# UDB5.net
KiCad netlist of a schematic drawn in EAGLE
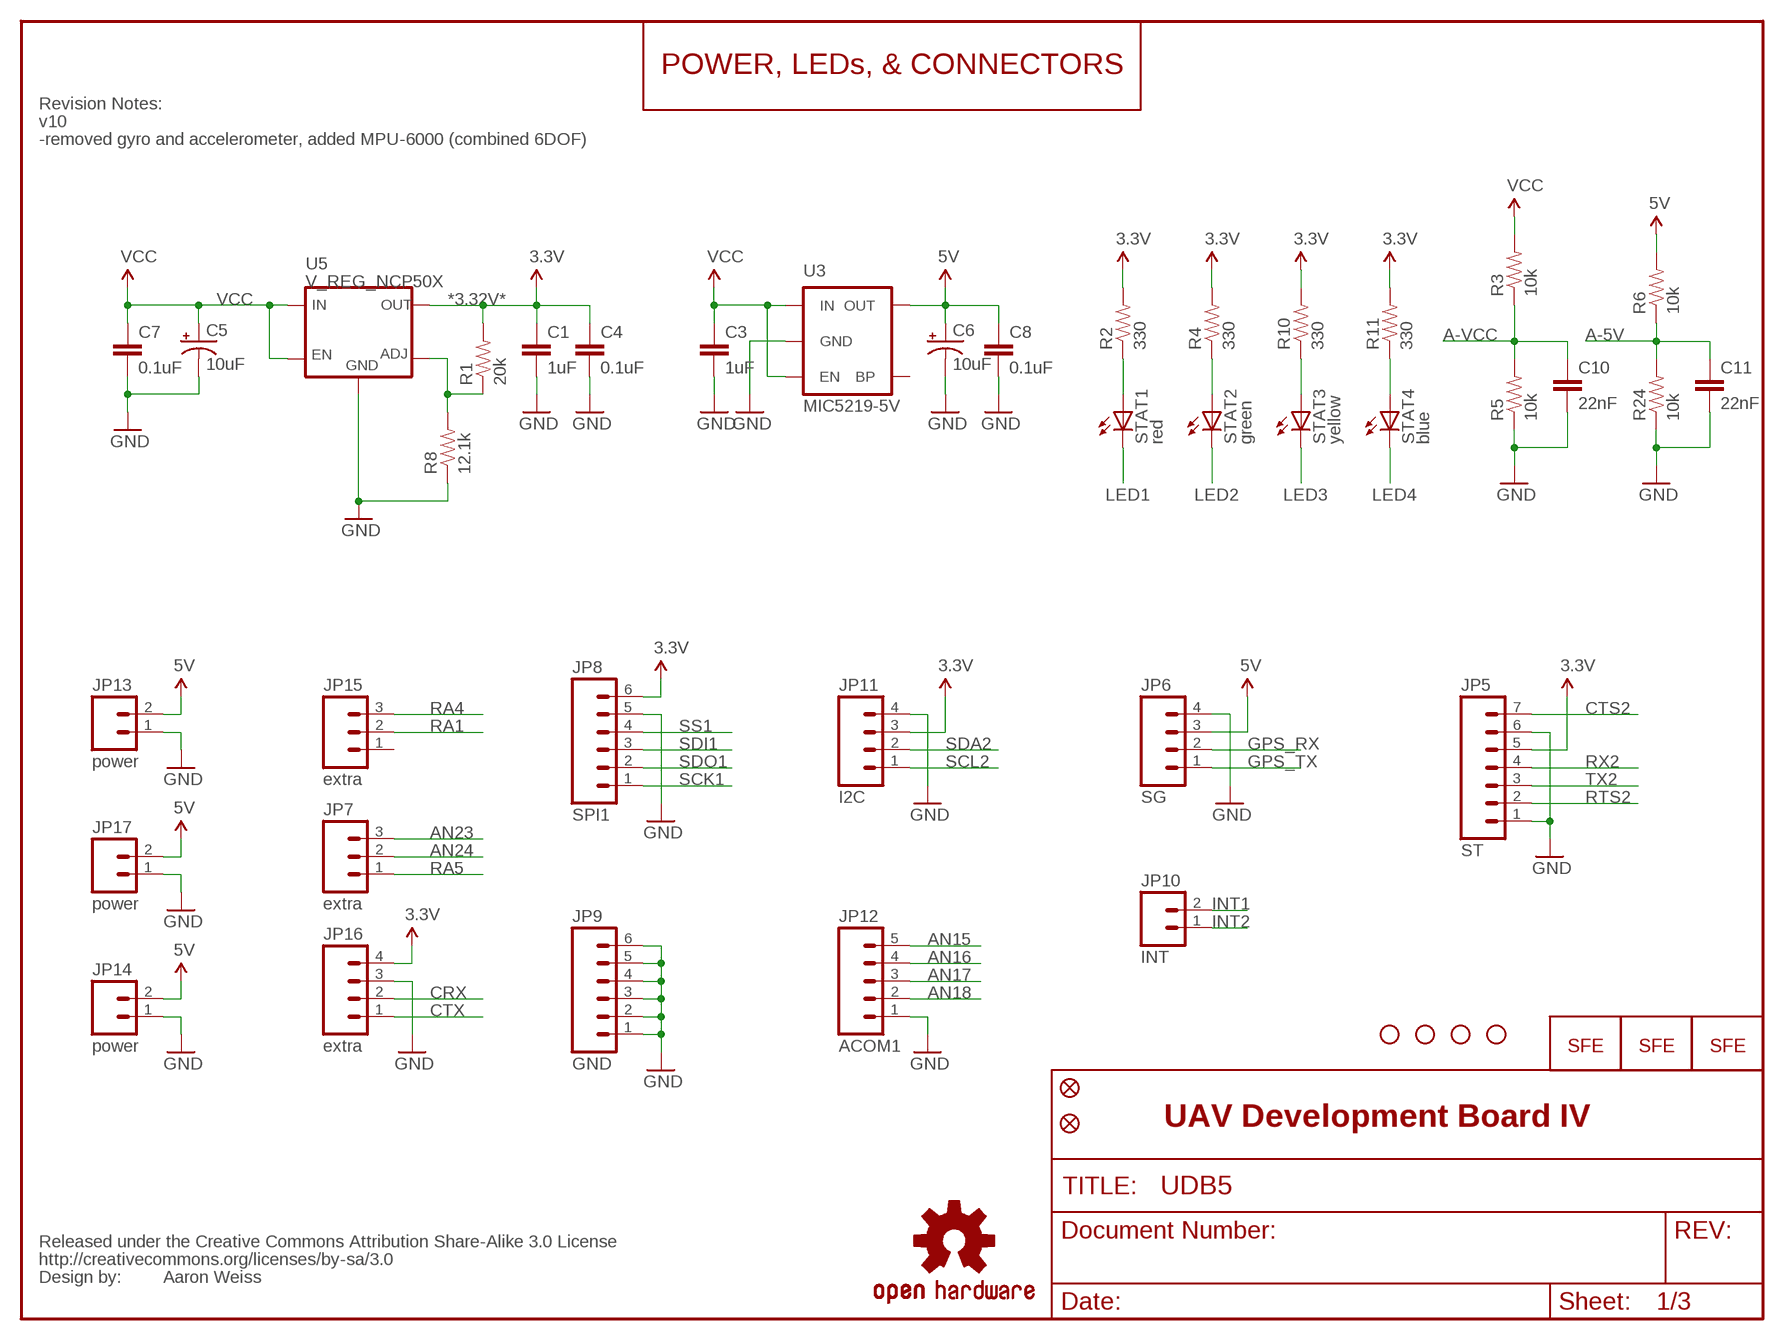
[diagram p0: schematic, sheet 1]
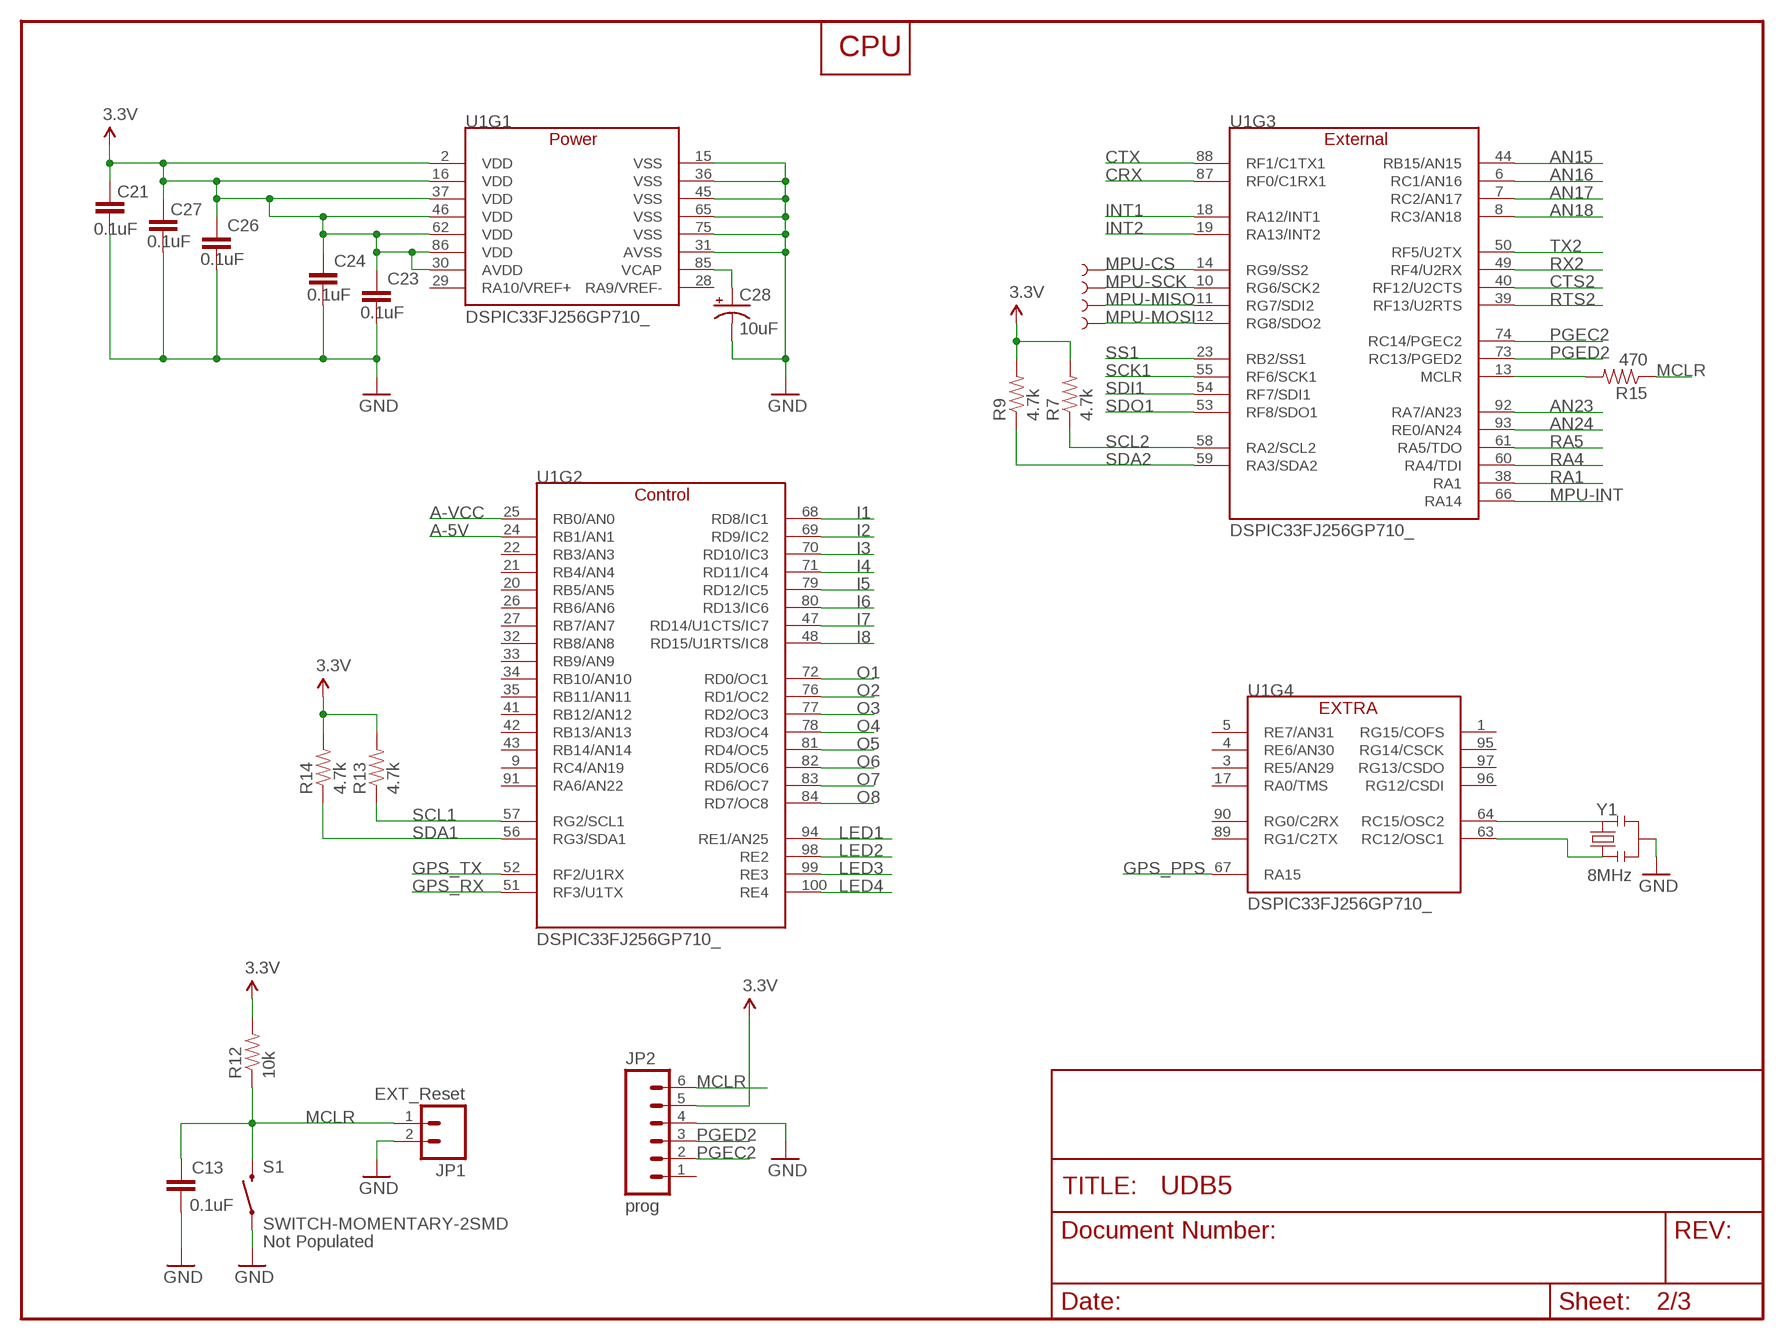
[diagram p1: schematic, sheet 2]
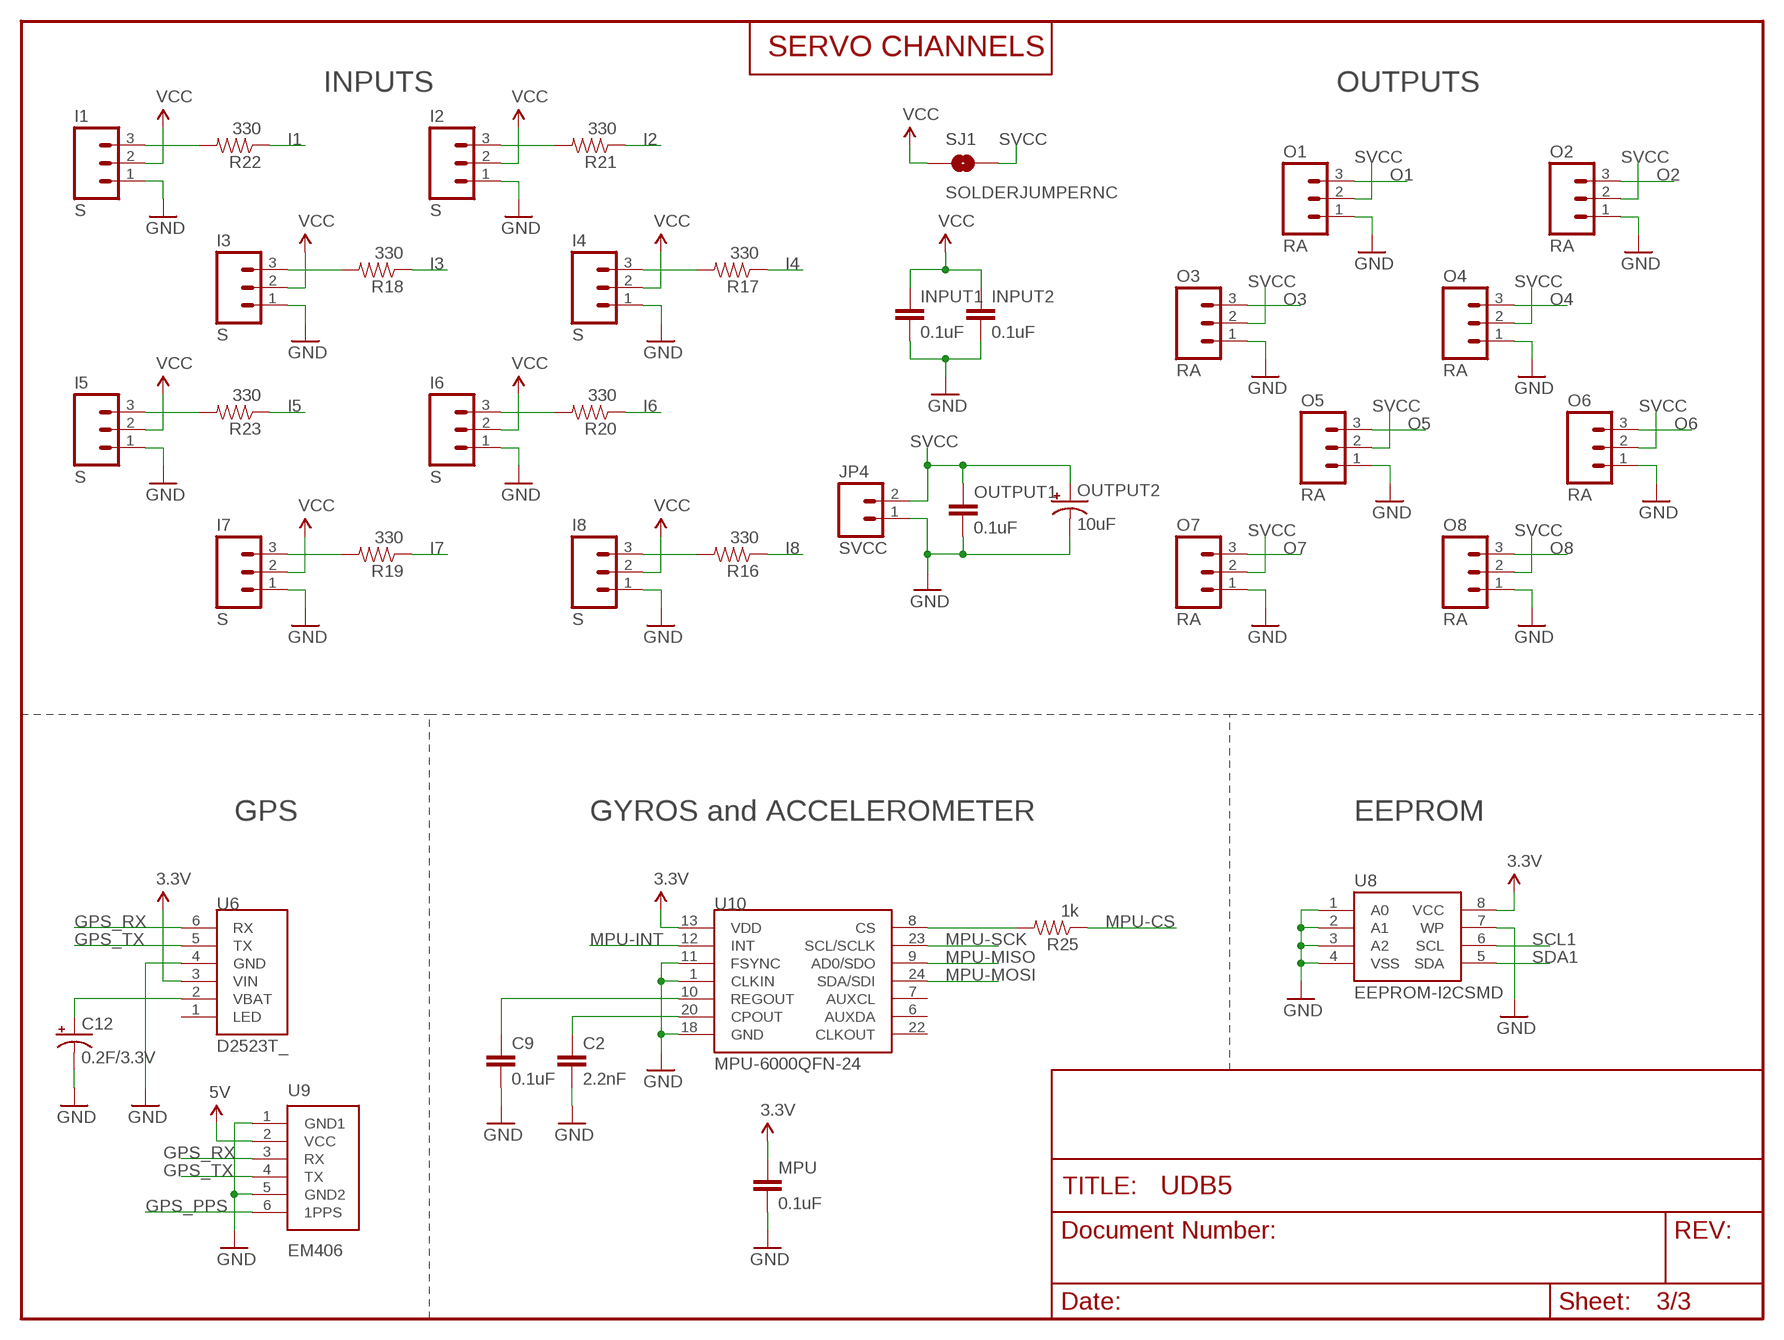
[diagram p2: schematic, sheet 3]

(export (version "E")
  (design (tool "Eeschema 10.0.6"))
  (components
    (comp (ref "C1")
      (value "1uF")
      (footprint "eagle-import:0402-CAP")
      (libsource (lib "eagle-import") (part "CAP0402-CAP"))
    )
    (comp (ref "C3")
      (value "1uF")
      (footprint "eagle-import:0402-CAP")
      (libsource (lib "eagle-import") (part "CAP0402-CAP"))
    )
    (comp (ref "C4")
      (value "0.1uF")
      (footprint "eagle-import:0402-CAP")
      (libsource (lib "eagle-import") (part "CAP0402-CAP"))
    )
    (comp (ref "C5")
      (value "10uF")
      (footprint "eagle-import:EIA3216")
      (libsource (lib "eagle-import") (part "CAP_POL1206"))
    )
    (comp (ref "C6")
      (value "10uF")
      (footprint "eagle-import:EIA3216")
      (libsource (lib "eagle-import") (part "CAP_POL1206"))
    )
    (comp (ref "C7")
      (value "0.1uF")
      (footprint "eagle-import:0402-CAP")
      (libsource (lib "eagle-import") (part "CAP0402-CAP"))
    )
    (comp (ref "C8")
      (value "0.1uF")
      (footprint "eagle-import:0402-CAP")
      (libsource (lib "eagle-import") (part "CAP0402-CAP"))
    )
    (comp (ref "C10")
      (value "22nF")
      (footprint "eagle-import:0402-CAP")
      (libsource (lib "eagle-import") (part "CAP0402-CAP"))
    )
    (comp (ref "C11")
      (value "22nF")
      (footprint "eagle-import:0402-CAP")
      (libsource (lib "eagle-import") (part "CAP0402-CAP"))
    )
    (comp (ref "CC_TEXT1")
      (value "CREATIVE_COMMONS")
      (footprint "eagle-import:CREATIVE_COMMONS")
      (libsource (lib "eagle-import") (part "CREATIVE_COMMONS"))
    )
    (comp (ref "JP3")
      (value "LOGO-SFENEW")
      (footprint "eagle-import:SFE-NEW-WEBLOGO")
      (libsource (lib "eagle-import") (part "LOGO-SFENEW"))
    )
    (comp (ref "JP5")
      (value "ST")
      (footprint "eagle-import:1X07")
      (libsource (lib "eagle-import") (part "M07"))
    )
    (comp (ref "JP6")
      (value "SG")
      (footprint "eagle-import:1X04")
      (libsource (lib "eagle-import") (part "M04PTH"))
    )
    (comp (ref "JP7")
      (value "extra")
      (footprint "eagle-import:1X03")
      (libsource (lib "eagle-import") (part "M03PTH"))
    )
    (comp (ref "JP8")
      (value "SPI1")
      (footprint "eagle-import:1X06")
      (libsource (lib "eagle-import") (part "M06SIP"))
    )
    (comp (ref "JP9")
      (value "GND")
      (footprint "eagle-import:1X06")
      (libsource (lib "eagle-import") (part "SparkFun-Connectors_M06SIP"))
    )
    (comp (ref "JP10")
      (value "INT")
      (footprint "eagle-import:1X02")
      (libsource (lib "eagle-import") (part "M02PTH"))
    )
    (comp (ref "JP11")
      (value "I2C")
      (footprint "eagle-import:1X04")
      (libsource (lib "eagle-import") (part "M04PTH"))
    )
    (comp (ref "JP12")
      (value "ACOM1")
      (footprint "eagle-import:1X05")
      (libsource (lib "eagle-import") (part "M05PTH"))
    )
    (comp (ref "JP13")
      (value "power")
      (footprint "eagle-import:1X02")
      (libsource (lib "eagle-import") (part "M02PTH"))
    )
    (comp (ref "JP14")
      (value "power")
      (footprint "eagle-import:1X02")
      (libsource (lib "eagle-import") (part "M02PTH"))
    )
    (comp (ref "JP15")
      (value "extra")
      (footprint "eagle-import:1X03")
      (libsource (lib "eagle-import") (part "M03PTH"))
    )
    (comp (ref "JP16")
      (value "extra")
      (footprint "eagle-import:1X04")
      (libsource (lib "eagle-import") (part "M04PTH"))
    )
    (comp (ref "JP17")
      (value "power")
      (footprint "eagle-import:1X02")
      (libsource (lib "eagle-import") (part "M02PTH"))
    )
    (comp (ref "JP18")
      (value "FIDUCIAL1X2.5")
      (footprint "eagle-import:FIDUCIAL-1X2.5")
      (libsource (lib "eagle-import") (part "FIDUCIAL1X2.5"))
    )
    (comp (ref "JP19")
      (value "FIDUCIAL1X2.5")
      (footprint "eagle-import:FIDUCIAL-1X2.5")
      (libsource (lib "eagle-import") (part "FIDUCIAL1X2.5"))
    )
    (comp (ref "LOGO1")
      (value "LOGO-SFENW2")
      (footprint "eagle-import:SFE-NEW-WEB")
      (libsource (lib "eagle-import") (part "SparkFun-Aesthetics_LOGO-SFENW2"))
    )
    (comp (ref "R1")
      (value "20k")
      (footprint "eagle-import:0402-RES")
      (libsource (lib "eagle-import") (part "RESISTOR0402-RES"))
    )
    (comp (ref "R2")
      (value "330")
      (footprint "eagle-import:0402-RES")
      (libsource (lib "eagle-import") (part "RESISTOR0402-RES"))
    )
    (comp (ref "R3")
      (value "10k")
      (footprint "eagle-import:0402-RES")
      (libsource (lib "eagle-import") (part "RESISTOR0402-RES"))
    )
    (comp (ref "R4")
      (value "330")
      (footprint "eagle-import:0402-RES")
      (libsource (lib "eagle-import") (part "RESISTOR0402-RES"))
    )
    (comp (ref "R5")
      (value "10k")
      (footprint "eagle-import:0402-RES")
      (libsource (lib "eagle-import") (part "RESISTOR0402-RES"))
    )
    (comp (ref "R6")
      (value "10k")
      (footprint "eagle-import:0402-RES")
      (libsource (lib "eagle-import") (part "RESISTOR0402-RES"))
    )
    (comp (ref "R8")
      (value "12.1k")
      (footprint "eagle-import:0402-RES")
      (libsource (lib "eagle-import") (part "RESISTOR0402-RES"))
    )
    (comp (ref "R10")
      (value "330")
      (footprint "eagle-import:0402-RES")
      (libsource (lib "eagle-import") (part "RESISTOR0402-RES"))
    )
    (comp (ref "R11")
      (value "330")
      (footprint "eagle-import:0402-RES")
      (libsource (lib "eagle-import") (part "RESISTOR0402-RES"))
    )
    (comp (ref "R24")
      (value "10k")
      (footprint "eagle-import:0402-RES")
      (libsource (lib "eagle-import") (part "RESISTOR0402-RES"))
    )
    (comp (ref "STAT1")
      (value "red")
      (footprint "eagle-import:LED-0603")
      (libsource (lib "eagle-import") (part "LED0603"))
    )
    (comp (ref "STAT2")
      (value "green")
      (footprint "eagle-import:LED-0603")
      (libsource (lib "eagle-import") (part "LED0603"))
    )
    (comp (ref "STAT3")
      (value "yellow")
      (footprint "eagle-import:LED-0603")
      (libsource (lib "eagle-import") (part "LED0603"))
    )
    (comp (ref "STAT4")
      (value "blue")
      (footprint "eagle-import:LED-0603")
      (libsource (lib "eagle-import") (part "LED0603"))
    )
    (comp (ref "U$2")
      (value "STAND-OFF")
      (footprint "eagle-import:STAND-OFF")
      (libsource (lib "eagle-import") (part "STAND-OFF"))
    )
    (comp (ref "U$3")
      (value "STAND-OFF")
      (footprint "eagle-import:STAND-OFF")
      (libsource (lib "eagle-import") (part "STAND-OFF"))
    )
    (comp (ref "U$4")
      (value "STAND-OFF")
      (footprint "eagle-import:STAND-OFF")
      (libsource (lib "eagle-import") (part "STAND-OFF"))
    )
    (comp (ref "U$5")
      (value "STAND-OFF")
      (footprint "eagle-import:STAND-OFF")
      (libsource (lib "eagle-import") (part "STAND-OFF"))
    )
    (comp (ref "U$9")
      (value "OSHW-LOGOS")
      (footprint "eagle-import:OSHW-LOGO-S")
      (libsource (lib "eagle-import") (part "OSHW-LOGOS"))
    )
    (comp (ref "U$10")
      (value "LOGO-SFESK")
      (footprint "eagle-import:SFE-LOGO-FLAME")
      (libsource (lib "eagle-import") (part "LOGO-SFESK"))
    )
    (comp (ref "U3")
      (value "V_REG_LDOSMD")
      (footprint "eagle-import:SOT23-5")
      (libsource (lib "eagle-import") (part "V_REG_LDOSMD"))
    )
    (comp (ref "U5")
      (value "V_REG_NCP50X")
      (footprint "eagle-import:DPAK-5")
      (libsource (lib "eagle-import") (part "V_REG_NCP50X"))
    )
    (comp (ref "C2")
      (value "2.2nF")
      (footprint "eagle-import:0402-CAP")
      (libsource (lib "eagle-import") (part "SparkFun-Capacitors_CAP0402-CAP"))
    )
    (comp (ref "C9")
      (value "0.1uF")
      (footprint "eagle-import:0402-CAP")
      (libsource (lib "eagle-import") (part "SparkFun-Capacitors_CAP0402-CAP"))
    )
    (comp (ref "C12")
      (value "0.2F/3.3V")
      (footprint "eagle-import:EN_J2")
      (libsource (lib "eagle-import") (part "SparkFun-Capacitors_CAP_POLEN_J2"))
    )
    (comp (ref "I1")
      (value "S")
      (footprint "eagle-import:1X03")
      (libsource (lib "eagle-import") (part "M03PTH"))
    )
    (comp (ref "I2")
      (value "S")
      (footprint "eagle-import:1X03")
      (libsource (lib "eagle-import") (part "M03PTH"))
    )
    (comp (ref "I3")
      (value "S")
      (footprint "eagle-import:1X03")
      (libsource (lib "eagle-import") (part "M03PTH"))
    )
    (comp (ref "I4")
      (value "S")
      (footprint "eagle-import:1X03")
      (libsource (lib "eagle-import") (part "M03PTH"))
    )
    (comp (ref "I5")
      (value "S")
      (footprint "eagle-import:1X03")
      (libsource (lib "eagle-import") (part "M03PTH"))
    )
    (comp (ref "I6")
      (value "S")
      (footprint "eagle-import:1X03")
      (libsource (lib "eagle-import") (part "M03PTH"))
    )
    (comp (ref "I7")
      (value "S")
      (footprint "eagle-import:1X03")
      (libsource (lib "eagle-import") (part "M03PTH"))
    )
    (comp (ref "I8")
      (value "S")
      (footprint "eagle-import:1X03")
      (libsource (lib "eagle-import") (part "M03PTH"))
    )
    (comp (ref "INPUT1")
      (value "0.1uF")
      (footprint "eagle-import:0402-CAP")
      (libsource (lib "eagle-import") (part "CAP0402-CAP"))
    )
    (comp (ref "INPUT2")
      (value "0.1uF")
      (footprint "eagle-import:0402-CAP")
      (libsource (lib "eagle-import") (part "CAP0402-CAP"))
    )
    (comp (ref "JP4")
      (value "SVCC")
      (footprint "eagle-import:1X02")
      (libsource (lib "eagle-import") (part "M02PTH"))
    )
    (comp (ref "MPU")
      (value "0.1uF")
      (footprint "eagle-import:0402-CAP")
      (libsource (lib "eagle-import") (part "CAP0402-CAP"))
    )
    (comp (ref "O1")
      (value "RA")
      (footprint "eagle-import:1X03")
      (libsource (lib "eagle-import") (part "M03PTH"))
    )
    (comp (ref "O2")
      (value "RA")
      (footprint "eagle-import:1X03")
      (libsource (lib "eagle-import") (part "M03PTH"))
    )
    (comp (ref "O3")
      (value "RA")
      (footprint "eagle-import:1X03")
      (libsource (lib "eagle-import") (part "M03PTH"))
    )
    (comp (ref "O4")
      (value "RA")
      (footprint "eagle-import:1X03")
      (libsource (lib "eagle-import") (part "M03PTH"))
    )
    (comp (ref "O5")
      (value "RA")
      (footprint "eagle-import:1X03")
      (libsource (lib "eagle-import") (part "M03PTH"))
    )
    (comp (ref "O6")
      (value "RA")
      (footprint "eagle-import:1X03")
      (libsource (lib "eagle-import") (part "M03PTH"))
    )
    (comp (ref "O7")
      (value "RA")
      (footprint "eagle-import:1X03")
      (libsource (lib "eagle-import") (part "M03PTH"))
    )
    (comp (ref "O8")
      (value "RA")
      (footprint "eagle-import:1X03")
      (libsource (lib "eagle-import") (part "M03PTH"))
    )
    (comp (ref "OUTPUT1")
      (value "0.1uF")
      (footprint "eagle-import:0402-CAP")
      (libsource (lib "eagle-import") (part "CAP0402-CAP"))
    )
    (comp (ref "OUTPUT2")
      (value "10uF")
      (footprint "eagle-import:EIA3216")
      (libsource (lib "eagle-import") (part "CAP_POL1206"))
    )
    (comp (ref "R16")
      (value "330")
      (footprint "eagle-import:0402-RES")
      (libsource (lib "eagle-import") (part "RESISTOR0402-RES"))
    )
    (comp (ref "R17")
      (value "330")
      (footprint "eagle-import:0402-RES")
      (libsource (lib "eagle-import") (part "RESISTOR0402-RES"))
    )
    (comp (ref "R18")
      (value "330")
      (footprint "eagle-import:0402-RES")
      (libsource (lib "eagle-import") (part "RESISTOR0402-RES"))
    )
    (comp (ref "R19")
      (value "330")
      (footprint "eagle-import:0402-RES")
      (libsource (lib "eagle-import") (part "RESISTOR0402-RES"))
    )
    (comp (ref "R20")
      (value "330")
      (footprint "eagle-import:0402-RES")
      (libsource (lib "eagle-import") (part "RESISTOR0402-RES"))
    )
    (comp (ref "R21")
      (value "330")
      (footprint "eagle-import:0402-RES")
      (libsource (lib "eagle-import") (part "RESISTOR0402-RES"))
    )
    (comp (ref "R22")
      (value "330")
      (footprint "eagle-import:0402-RES")
      (libsource (lib "eagle-import") (part "RESISTOR0402-RES"))
    )
    (comp (ref "R23")
      (value "330")
      (footprint "eagle-import:0402-RES")
      (libsource (lib "eagle-import") (part "RESISTOR0402-RES"))
    )
    (comp (ref "R25")
      (value "1k")
      (footprint "eagle-import:0402-RES")
      (libsource (lib "eagle-import") (part "RESISTOR0402-RES"))
    )
    (comp (ref "SJ1")
      (value "SOLDERJUMPERNC")
      (footprint "eagle-import:SJ_2S")
      (libsource (lib "eagle-import") (part "SOLDERJUMPERNC"))
    )
    (comp (ref "U6")
      (value "D2523T_")
      (footprint "eagle-import:EM406")
      (libsource (lib "eagle-import") (part "D2523T_"))
    )
    (comp (ref "U8")
      (value "EEPROM-I2CSMD")
      (footprint "eagle-import:SO08")
      (libsource (lib "eagle-import") (part "EEPROM-I2CSMD"))
    )
    (comp (ref "U9")
      (value "EM406")
      (footprint "eagle-import:EM406")
      (libsource (lib "eagle-import") (part "EM406"))
    )
    (comp (ref "U10")
      (value "MPU-6000QFN-24")
      (footprint "eagle-import:QFN-24-TESTING")
      (libsource (lib "eagle-import") (part "MPU-6000QFN-24"))
    )
    (comp (ref "C13")
      (value "0.1uF")
      (footprint "eagle-import:0402-CAP")
      (libsource (lib "eagle-import") (part "CAP0402-CAP"))
    )
    (comp (ref "C21")
      (value "0.1uF")
      (footprint "eagle-import:0402-CAP")
      (libsource (lib "eagle-import") (part "CAP0402-CAP"))
    )
    (comp (ref "C23")
      (value "0.1uF")
      (footprint "eagle-import:0402-CAP")
      (libsource (lib "eagle-import") (part "CAP0402-CAP"))
    )
    (comp (ref "C24")
      (value "0.1uF")
      (footprint "eagle-import:0402-CAP")
      (libsource (lib "eagle-import") (part "CAP0402-CAP"))
    )
    (comp (ref "C26")
      (value "0.1uF")
      (footprint "eagle-import:0402-CAP")
      (libsource (lib "eagle-import") (part "CAP0402-CAP"))
    )
    (comp (ref "C27")
      (value "0.1uF")
      (footprint "eagle-import:0402-CAP")
      (libsource (lib "eagle-import") (part "CAP0402-CAP"))
    )
    (comp (ref "C28")
      (value "10uF")
      (footprint "eagle-import:EIA3216")
      (libsource (lib "eagle-import") (part "CAP_POL1206"))
    )
    (comp (ref "JP1")
      (value "EXT_Reset")
      (footprint "eagle-import:1X02")
      (libsource (lib "eagle-import") (part "M02PTH"))
    )
    (comp (ref "JP2")
      (value "prog")
      (footprint "eagle-import:1X06")
      (libsource (lib "eagle-import") (part "M06SIP"))
    )
    (comp (ref "R7")
      (value "4.7k")
      (footprint "eagle-import:0402-RES")
      (libsource (lib "eagle-import") (part "RESISTOR0402-RES"))
    )
    (comp (ref "R9")
      (value "4.7k")
      (footprint "eagle-import:0402-RES")
      (libsource (lib "eagle-import") (part "RESISTOR0402-RES"))
    )
    (comp (ref "R12")
      (value "10k")
      (footprint "eagle-import:0402-RES")
      (libsource (lib "eagle-import") (part "RESISTOR0402-RES"))
    )
    (comp (ref "R13")
      (value "4.7k")
      (footprint "eagle-import:0402-RES")
      (libsource (lib "eagle-import") (part "RESISTOR0402-RES"))
    )
    (comp (ref "R14")
      (value "4.7k")
      (footprint "eagle-import:0402-RES")
      (libsource (lib "eagle-import") (part "RESISTOR0402-RES"))
    )
    (comp (ref "R15")
      (value "470")
      (footprint "eagle-import:0402-RES")
      (libsource (lib "eagle-import") (part "RESISTOR0402-RES"))
    )
    (comp (ref "S1")
      (value "SWITCH-MOMENTARY-2SMD")
      (footprint "eagle-import:TACTILE_SWITCH_SMD")
      (libsource (lib "eagle-import") (part "SWITCH-MOMENTARY-2SMD"))
    )
    (comp (ref "TP1")
      (value "TEST-POINT3")
      (footprint "eagle-import:PAD.03X.03")
      (libsource (lib "eagle-import") (part "TEST-POINT3"))
    )
    (comp (ref "TP2")
      (value "TEST-POINT3")
      (footprint "eagle-import:PAD.03X.03")
      (libsource (lib "eagle-import") (part "TEST-POINT3"))
    )
    (comp (ref "TP3")
      (value "TEST-POINT3")
      (footprint "eagle-import:PAD.03X.03")
      (libsource (lib "eagle-import") (part "TEST-POINT3"))
    )
    (comp (ref "TP4")
      (value "TEST-POINT3")
      (footprint "eagle-import:PAD.03X.03")
      (libsource (lib "eagle-import") (part "TEST-POINT3"))
    )
    (comp (ref "U1")
      (value "DSPIC33FJ256GP710_")
      (footprint "eagle-import:TQFP-100-12X12MM")
      (libsource (lib "eagle-import") (part "DSPIC33FJ256GP710_"))
    )
    (comp (ref "Y1")
      (value "RESONATORSMD")
      (footprint "eagle-import:RESONATOR-SMD")
      (libsource (lib "eagle-import") (part "RESONATORSMD"))
    )
  )
  (nets
    (net (code "1") (name "3.3V") (class "Default")
      (node (ref "C1") (pin "1") (pinfunction "1_1") (pintype "passive"))
      (node (ref "C21") (pin "1") (pinfunction "1_1") (pintype "passive"))
      (node (ref "C23") (pin "1") (pinfunction "1_1") (pintype "passive"))
      (node (ref "C24") (pin "1") (pinfunction "1_1") (pintype "passive"))
      (node (ref "C26") (pin "1") (pinfunction "1_1") (pintype "passive"))
      (node (ref "C27") (pin "1") (pinfunction "1_1") (pintype "passive"))
      (node (ref "C4") (pin "1") (pinfunction "1_1") (pintype "passive"))
      (node (ref "JP11") (pin "3") (pinfunction "3_3") (pintype "passive"))
      (node (ref "JP16") (pin "4") (pinfunction "4_4") (pintype "passive"))
      (node (ref "JP2") (pin "5") (pinfunction "5_5") (pintype "passive"))
      (node (ref "JP5") (pin "5") (pinfunction "5_5") (pintype "passive"))
      (node (ref "JP8") (pin "6") (pinfunction "6_6") (pintype "passive"))
      (node (ref "MPU") (pin "1") (pinfunction "1_1") (pintype "passive"))
      (node (ref "R1") (pin "2") (pinfunction "2_2") (pintype "passive"))
      (node (ref "R10") (pin "2") (pinfunction "2_2") (pintype "passive"))
      (node (ref "R11") (pin "2") (pinfunction "2_2") (pintype "passive"))
      (node (ref "R12") (pin "2") (pinfunction "2_2") (pintype "passive"))
      (node (ref "R13") (pin "2") (pinfunction "2_2") (pintype "passive"))
      (node (ref "R14") (pin "2") (pinfunction "2_2") (pintype "passive"))
      (node (ref "R2") (pin "2") (pinfunction "2_2") (pintype "passive"))
      (node (ref "R4") (pin "2") (pinfunction "2_2") (pintype "passive"))
      (node (ref "R7") (pin "2") (pinfunction "2_2") (pintype "passive"))
      (node (ref "R9") (pin "2") (pinfunction "2_2") (pintype "passive"))
      (node (ref "U1") (pin "16") (pinfunction "VDD_16") (pintype "bidirectional"))
      (node (ref "U1") (pin "2") (pinfunction "VDD_2") (pintype "bidirectional"))
      (node (ref "U1") (pin "30") (pinfunction "AVDD_30") (pintype "bidirectional"))
      (node (ref "U1") (pin "37") (pinfunction "VDD_37") (pintype "bidirectional"))
      (node (ref "U1") (pin "46") (pinfunction "VDD_46") (pintype "bidirectional"))
      (node (ref "U1") (pin "62") (pinfunction "VDD_62") (pintype "bidirectional"))
      (node (ref "U1") (pin "86") (pinfunction "VDD_86") (pintype "bidirectional"))
      (node (ref "U10") (pin "13") (pinfunction "VDD_13") (pintype "bidirectional"))
      (node (ref "U5") (pin "VOUT") (pinfunction "OUT_VOUT") (pintype "output"))
      (node (ref "U6") (pin "3") (pinfunction "VIN_3") (pintype "bidirectional"))
      (node (ref "U8") (pin "8") (pinfunction "VCC_8") (pintype "power_in"))
    )
    (net (code "2") (name "5V") (class "Default")
      (node (ref "C6") (pin "A") (pinfunction "+_A") (pintype "passive"))
      (node (ref "C8") (pin "1") (pinfunction "1_1") (pintype "passive"))
      (node (ref "JP13") (pin "2") (pinfunction "2_2") (pintype "passive"))
      (node (ref "JP14") (pin "2") (pinfunction "2_2") (pintype "passive"))
      (node (ref "JP17") (pin "2") (pinfunction "2_2") (pintype "passive"))
      (node (ref "JP6") (pin "3") (pinfunction "3_3") (pintype "passive"))
      (node (ref "R6") (pin "2") (pinfunction "2_2") (pintype "passive"))
      (node (ref "U3") (pin "5") (pinfunction "OUT_5") (pintype "passive"))
      (node (ref "U9") (pin "2") (pinfunction "VCC_2") (pintype "bidirectional"))
    )
    (net (code "3") (name "A-5V") (class "Default")
      (node (ref "C11") (pin "1") (pinfunction "1_1") (pintype "passive"))
      (node (ref "R24") (pin "2") (pinfunction "2_2") (pintype "passive"))
      (node (ref "R6") (pin "1") (pinfunction "1_1") (pintype "passive"))
      (node (ref "U1") (pin "24") (pinfunction "RB1/AN1_24") (pintype "bidirectional"))
    )
    (net (code "4") (name "A-VCC") (class "Default")
      (node (ref "C10") (pin "1") (pinfunction "1_1") (pintype "passive"))
      (node (ref "R3") (pin "1") (pinfunction "1_1") (pintype "passive"))
      (node (ref "R5") (pin "2") (pinfunction "2_2") (pintype "passive"))
      (node (ref "U1") (pin "25") (pinfunction "RB0/AN0_25") (pintype "bidirectional"))
    )
    (net (code "5") (name "AN15") (class "Default")
      (node (ref "JP12") (pin "5") (pinfunction "5_5") (pintype "passive"))
      (node (ref "U1") (pin "44") (pinfunction "RB15/AN15_44") (pintype "bidirectional"))
    )
    (net (code "6") (name "AN16") (class "Default")
      (node (ref "JP12") (pin "4") (pinfunction "4_4") (pintype "passive"))
      (node (ref "U1") (pin "6") (pinfunction "RC1/AN16_6") (pintype "bidirectional"))
    )
    (net (code "7") (name "AN17") (class "Default")
      (node (ref "JP12") (pin "3") (pinfunction "3_3") (pintype "passive"))
      (node (ref "U1") (pin "7") (pinfunction "RC2/AN17_7") (pintype "bidirectional"))
    )
    (net (code "8") (name "AN18") (class "Default")
      (node (ref "JP12") (pin "2") (pinfunction "2_2") (pintype "passive"))
      (node (ref "U1") (pin "8") (pinfunction "RC3/AN18_8") (pintype "bidirectional"))
    )
    (net (code "9") (name "AN23") (class "Default")
      (node (ref "JP7") (pin "3") (pinfunction "3_3") (pintype "passive"))
      (node (ref "U1") (pin "92") (pinfunction "RA7/AN23_92") (pintype "bidirectional"))
    )
    (net (code "10") (name "AN24") (class "Default")
      (node (ref "JP7") (pin "2") (pinfunction "2_2") (pintype "passive"))
      (node (ref "U1") (pin "93") (pinfunction "RE0/AN24_93") (pintype "bidirectional"))
    )
    (net (code "11") (name "CRX") (class "Default")
      (node (ref "JP16") (pin "2") (pinfunction "2_2") (pintype "passive"))
      (node (ref "U1") (pin "87") (pinfunction "RF0/C1RX1_87") (pintype "bidirectional"))
    )
    (net (code "12") (name "CTS2") (class "Default")
      (node (ref "JP5") (pin "7") (pinfunction "7_7") (pintype "passive"))
      (node (ref "U1") (pin "40") (pinfunction "RF12/U2CTS_40") (pintype "bidirectional"))
    )
    (net (code "13") (name "CTX") (class "Default")
      (node (ref "JP16") (pin "1") (pinfunction "1_1") (pintype "passive"))
      (node (ref "U1") (pin "88") (pinfunction "RF1/C1TX1_88") (pintype "bidirectional"))
    )
    (net (code "14") (name "GND") (class "Default")
      (node (ref "C1") (pin "2") (pinfunction "2_2") (pintype "passive"))
      (node (ref "C10") (pin "2") (pinfunction "2_2") (pintype "passive"))
      (node (ref "C11") (pin "2") (pinfunction "2_2") (pintype "passive"))
      (node (ref "C12") (pin "-") (pinfunction "-_-") (pintype "passive"))
      (node (ref "C13") (pin "2") (pinfunction "2_2") (pintype "passive"))
      (node (ref "C2") (pin "2") (pinfunction "2_2") (pintype "passive"))
      (node (ref "C21") (pin "2") (pinfunction "2_2") (pintype "passive"))
      (node (ref "C23") (pin "2") (pinfunction "2_2") (pintype "passive"))
      (node (ref "C24") (pin "2") (pinfunction "2_2") (pintype "passive"))
      (node (ref "C26") (pin "2") (pinfunction "2_2") (pintype "passive"))
      (node (ref "C27") (pin "2") (pinfunction "2_2") (pintype "passive"))
      (node (ref "C28") (pin "C") (pinfunction "-_C") (pintype "passive"))
      (node (ref "C3") (pin "2") (pinfunction "2_2") (pintype "passive"))
      (node (ref "C4") (pin "2") (pinfunction "2_2") (pintype "passive"))
      (node (ref "C5") (pin "C") (pinfunction "-_C") (pintype "passive"))
      (node (ref "C6") (pin "C") (pinfunction "-_C") (pintype "passive"))
      (node (ref "C7") (pin "2") (pinfunction "2_2") (pintype "passive"))
      (node (ref "C8") (pin "2") (pinfunction "2_2") (pintype "passive"))
      (node (ref "C9") (pin "2") (pinfunction "2_2") (pintype "passive"))
      (node (ref "I1") (pin "1") (pinfunction "1_1") (pintype "passive"))
      (node (ref "I2") (pin "1") (pinfunction "1_1") (pintype "passive"))
      (node (ref "I3") (pin "1") (pinfunction "1_1") (pintype "passive"))
      (node (ref "I4") (pin "1") (pinfunction "1_1") (pintype "passive"))
      (node (ref "I5") (pin "1") (pinfunction "1_1") (pintype "passive"))
      (node (ref "I6") (pin "1") (pinfunction "1_1") (pintype "passive"))
      (node (ref "I7") (pin "1") (pinfunction "1_1") (pintype "passive"))
      (node (ref "I8") (pin "1") (pinfunction "1_1") (pintype "passive"))
      (node (ref "INPUT1") (pin "2") (pinfunction "2_2") (pintype "passive"))
      (node (ref "INPUT2") (pin "2") (pinfunction "2_2") (pintype "passive"))
      (node (ref "JP1") (pin "2") (pinfunction "2_2") (pintype "passive"))
      (node (ref "JP11") (pin "4") (pinfunction "4_4") (pintype "passive"))
      (node (ref "JP12") (pin "1") (pinfunction "1_1") (pintype "passive"))
      (node (ref "JP13") (pin "1") (pinfunction "1_1") (pintype "passive"))
      (node (ref "JP14") (pin "1") (pinfunction "1_1") (pintype "passive"))
      (node (ref "JP16") (pin "3") (pinfunction "3_3") (pintype "passive"))
      (node (ref "JP17") (pin "1") (pinfunction "1_1") (pintype "passive"))
      (node (ref "JP2") (pin "4") (pinfunction "4_4") (pintype "passive"))
      (node (ref "JP4") (pin "1") (pinfunction "1_1") (pintype "passive"))
      (node (ref "JP5") (pin "1") (pinfunction "1_1") (pintype "passive"))
      (node (ref "JP5") (pin "6") (pinfunction "6_6") (pintype "passive"))
      (node (ref "JP6") (pin "4") (pinfunction "4_4") (pintype "passive"))
      (node (ref "JP8") (pin "5") (pinfunction "5_5") (pintype "passive"))
      (node (ref "JP9") (pin "1") (pinfunction "1_1") (pintype "passive"))
      (node (ref "JP9") (pin "2") (pinfunction "2_2") (pintype "passive"))
      (node (ref "JP9") (pin "3") (pinfunction "3_3") (pintype "passive"))
      (node (ref "JP9") (pin "4") (pinfunction "4_4") (pintype "passive"))
      (node (ref "JP9") (pin "5") (pinfunction "5_5") (pintype "passive"))
      (node (ref "JP9") (pin "6") (pinfunction "6_6") (pintype "passive"))
      (node (ref "MPU") (pin "2") (pinfunction "2_2") (pintype "passive"))
      (node (ref "O1") (pin "1") (pinfunction "1_1") (pintype "passive"))
      (node (ref "O2") (pin "1") (pinfunction "1_1") (pintype "passive"))
      (node (ref "O3") (pin "1") (pinfunction "1_1") (pintype "passive"))
      (node (ref "O4") (pin "1") (pinfunction "1_1") (pintype "passive"))
      (node (ref "O5") (pin "1") (pinfunction "1_1") (pintype "passive"))
      (node (ref "O6") (pin "1") (pinfunction "1_1") (pintype "passive"))
      (node (ref "O7") (pin "1") (pinfunction "1_1") (pintype "passive"))
      (node (ref "O8") (pin "1") (pinfunction "1_1") (pintype "passive"))
      (node (ref "OUTPUT1") (pin "2") (pinfunction "2_2") (pintype "passive"))
      (node (ref "OUTPUT2") (pin "C") (pinfunction "-_C") (pintype "passive"))
      (node (ref "R24") (pin "1") (pinfunction "1_1") (pintype "passive"))
      (node (ref "R5") (pin "1") (pinfunction "1_1") (pintype "passive"))
      (node (ref "R8") (pin "1") (pinfunction "1_1") (pintype "passive"))
      (node (ref "S1") (pin "1") (pinfunction "1_1") (pintype "passive"))
      (node (ref "U1") (pin "15") (pinfunction "VSS_15") (pintype "bidirectional"))
      (node (ref "U1") (pin "31") (pinfunction "AVSS_31") (pintype "bidirectional"))
      (node (ref "U1") (pin "36") (pinfunction "VSS_36") (pintype "bidirectional"))
      (node (ref "U1") (pin "45") (pinfunction "VSS_45") (pintype "bidirectional"))
      (node (ref "U1") (pin "65") (pinfunction "VSS_65") (pintype "bidirectional"))
      (node (ref "U1") (pin "75") (pinfunction "VSS_75") (pintype "bidirectional"))
      (node (ref "U10") (pin "1") (pinfunction "CLKIN_1") (pintype "bidirectional"))
      (node (ref "U10") (pin "11") (pinfunction "FSYNC_11") (pintype "bidirectional"))
      (node (ref "U10") (pin "18") (pinfunction "GND_18") (pintype "bidirectional"))
      (node (ref "U3") (pin "2") (pinfunction "GND_2") (pintype "input"))
      (node (ref "U5") (pin "GND") (pinfunction "GND_GND") (pintype "bidirectional"))
      (node (ref "U6") (pin "4") (pinfunction "GND_4") (pintype "bidirectional"))
      (node (ref "U8") (pin "1") (pinfunction "A0_1") (pintype "bidirectional"))
      (node (ref "U8") (pin "2") (pinfunction "A1_2") (pintype "bidirectional"))
      (node (ref "U8") (pin "3") (pinfunction "A2_3") (pintype "bidirectional"))
      (node (ref "U8") (pin "4") (pinfunction "VSS_4") (pintype "power_in"))
      (node (ref "U8") (pin "7") (pinfunction "WP_7") (pintype "bidirectional"))
      (node (ref "U9") (pin "1") (pinfunction "GND1_1") (pintype "bidirectional"))
      (node (ref "U9") (pin "5") (pinfunction "GND2_5") (pintype "bidirectional"))
      (node (ref "Y1") (pin "2") (pinfunction "2_2") (pintype "passive"))
    )
    (net (code "15") (name "GPS_PPS") (class "Default")
      (node (ref "U1") (pin "67") (pinfunction "RA15_67") (pintype "bidirectional"))
      (node (ref "U9") (pin "6") (pinfunction "1PPS_6") (pintype "bidirectional"))
    )
    (net (code "16") (name "GPS_RX") (class "Default")
      (node (ref "JP6") (pin "2") (pinfunction "2_2") (pintype "passive"))
      (node (ref "U1") (pin "51") (pinfunction "RF3/U1TX_51") (pintype "bidirectional"))
      (node (ref "U6") (pin "6") (pinfunction "RX_6") (pintype "bidirectional"))
      (node (ref "U9") (pin "3") (pinfunction "RX_3") (pintype "bidirectional"))
    )
    (net (code "17") (name "GPS_TX") (class "Default")
      (node (ref "JP6") (pin "1") (pinfunction "1_1") (pintype "passive"))
      (node (ref "U1") (pin "52") (pinfunction "RF2/U1RX_52") (pintype "bidirectional"))
      (node (ref "U6") (pin "5") (pinfunction "TX_5") (pintype "bidirectional"))
      (node (ref "U9") (pin "4") (pinfunction "TX_4") (pintype "bidirectional"))
    )
    (net (code "18") (name "I1") (class "Default")
      (node (ref "R22") (pin "1") (pinfunction "1_1") (pintype "passive"))
      (node (ref "U1") (pin "68") (pinfunction "RD8/IC1_68") (pintype "bidirectional"))
    )
    (net (code "19") (name "I2") (class "Default")
      (node (ref "R21") (pin "1") (pinfunction "1_1") (pintype "passive"))
      (node (ref "U1") (pin "69") (pinfunction "RD9/IC2_69") (pintype "bidirectional"))
    )
    (net (code "20") (name "I3") (class "Default")
      (node (ref "R18") (pin "1") (pinfunction "1_1") (pintype "passive"))
      (node (ref "U1") (pin "70") (pinfunction "RD10/IC3_70") (pintype "bidirectional"))
    )
    (net (code "21") (name "I4") (class "Default")
      (node (ref "R17") (pin "1") (pinfunction "1_1") (pintype "passive"))
      (node (ref "U1") (pin "71") (pinfunction "RD11/IC4_71") (pintype "bidirectional"))
    )
    (net (code "22") (name "I5") (class "Default")
      (node (ref "R23") (pin "1") (pinfunction "1_1") (pintype "passive"))
      (node (ref "U1") (pin "79") (pinfunction "RD12/IC5_79") (pintype "bidirectional"))
    )
    (net (code "23") (name "I6") (class "Default")
      (node (ref "R20") (pin "1") (pinfunction "1_1") (pintype "passive"))
      (node (ref "U1") (pin "80") (pinfunction "RD13/IC6_80") (pintype "bidirectional"))
    )
    (net (code "24") (name "I7") (class "Default")
      (node (ref "R19") (pin "1") (pinfunction "1_1") (pintype "passive"))
      (node (ref "U1") (pin "47") (pinfunction "RD14/U1CTS/IC7_47") (pintype "bidirectional"))
    )
    (net (code "25") (name "I8") (class "Default")
      (node (ref "R16") (pin "1") (pinfunction "1_1") (pintype "passive"))
      (node (ref "U1") (pin "48") (pinfunction "RD15/U1RTS/IC8_48") (pintype "bidirectional"))
    )
    (net (code "26") (name "INT1") (class "Default")
      (node (ref "JP10") (pin "2") (pinfunction "2_2") (pintype "passive"))
      (node (ref "U1") (pin "18") (pinfunction "RA12/INT1_18") (pintype "bidirectional"))
    )
    (net (code "27") (name "INT2") (class "Default")
      (node (ref "JP10") (pin "1") (pinfunction "1_1") (pintype "passive"))
      (node (ref "U1") (pin "19") (pinfunction "RA13/INT2_19") (pintype "bidirectional"))
    )
    (net (code "28") (name "LED1") (class "Default")
      (node (ref "STAT1") (pin "C") (pinfunction "C_C") (pintype "passive"))
      (node (ref "U1") (pin "94") (pinfunction "RE1/AN25_94") (pintype "bidirectional"))
    )
    (net (code "29") (name "LED2") (class "Default")
      (node (ref "STAT2") (pin "C") (pinfunction "C_C") (pintype "passive"))
      (node (ref "U1") (pin "98") (pinfunction "RE2_98") (pintype "bidirectional"))
    )
    (net (code "30") (name "LED3") (class "Default")
      (node (ref "STAT3") (pin "C") (pinfunction "C_C") (pintype "passive"))
      (node (ref "U1") (pin "99") (pinfunction "RE3_99") (pintype "bidirectional"))
    )
    (net (code "31") (name "LED4") (class "Default")
      (node (ref "STAT4") (pin "C") (pinfunction "C_C") (pintype "passive"))
      (node (ref "U1") (pin "100") (pinfunction "RE4_100") (pintype "bidirectional"))
    )
    (net (code "32") (name "MCLR") (class "Default")
      (node (ref "C13") (pin "1") (pinfunction "1_1") (pintype "passive"))
      (node (ref "JP1") (pin "1") (pinfunction "1_1") (pintype "passive"))
      (node (ref "JP2") (pin "6") (pinfunction "6_6") (pintype "passive"))
      (node (ref "R12") (pin "1") (pinfunction "1_1") (pintype "passive"))
      (node (ref "R15") (pin "1") (pinfunction "1_1") (pintype "passive"))
      (node (ref "S1") (pin "3") (pinfunction "2_3") (pintype "passive"))
    )
    (net (code "33") (name "MPU-CS") (class "Default")
      (node (ref "R25") (pin "1") (pinfunction "1_1") (pintype "passive"))
      (node (ref "TP1") (pin "P$1") (pinfunction "1_P$1") (pintype "bidirectional"))
      (node (ref "U1") (pin "14") (pinfunction "RG9/SS2_14") (pintype "bidirectional"))
    )
    (net (code "34") (name "MPU-INT") (class "Default")
      (node (ref "U1") (pin "66") (pinfunction "RA14_66") (pintype "bidirectional"))
      (node (ref "U10") (pin "12") (pinfunction "INT_12") (pintype "bidirectional"))
    )
    (net (code "35") (name "MPU-MISO") (class "Default")
      (node (ref "TP3") (pin "P$1") (pinfunction "1_P$1") (pintype "bidirectional"))
      (node (ref "U1") (pin "11") (pinfunction "RG7/SDI2_11") (pintype "bidirectional"))
      (node (ref "U10") (pin "9") (pinfunction "AD0/SDO_9") (pintype "bidirectional"))
    )
    (net (code "36") (name "MPU-MOSI") (class "Default")
      (node (ref "TP4") (pin "P$1") (pinfunction "1_P$1") (pintype "bidirectional"))
      (node (ref "U1") (pin "12") (pinfunction "RG8/SDO2_12") (pintype "bidirectional"))
      (node (ref "U10") (pin "24") (pinfunction "SDA/SDI_24") (pintype "bidirectional"))
    )
    (net (code "37") (name "MPU-SCK") (class "Default")
      (node (ref "TP2") (pin "P$1") (pinfunction "1_P$1") (pintype "bidirectional"))
      (node (ref "U1") (pin "10") (pinfunction "RG6/SCK2_10") (pintype "bidirectional"))
      (node (ref "U10") (pin "23") (pinfunction "SCL/SCLK_23") (pintype "bidirectional"))
    )
    (net (code "38") (name "Net-(C28-+)") (class "Default")
      (node (ref "C28") (pin "A") (pinfunction "+_A") (pintype "passive"))
      (node (ref "U1") (pin "85") (pinfunction "VCAP_85") (pintype "bidirectional"))
    )
    (net (code "39") (name "Net-(I1-Pad3)") (class "Default")
      (node (ref "I1") (pin "3") (pinfunction "3_3") (pintype "passive"))
      (node (ref "R22") (pin "2") (pinfunction "2_2") (pintype "passive"))
    )
    (net (code "40") (name "Net-(I2-Pad3)") (class "Default")
      (node (ref "I2") (pin "3") (pinfunction "3_3") (pintype "passive"))
      (node (ref "R21") (pin "2") (pinfunction "2_2") (pintype "passive"))
    )
    (net (code "41") (name "Net-(I3-Pad3)") (class "Default")
      (node (ref "I3") (pin "3") (pinfunction "3_3") (pintype "passive"))
      (node (ref "R18") (pin "2") (pinfunction "2_2") (pintype "passive"))
    )
    (net (code "42") (name "Net-(I4-Pad3)") (class "Default")
      (node (ref "I4") (pin "3") (pinfunction "3_3") (pintype "passive"))
      (node (ref "R17") (pin "2") (pinfunction "2_2") (pintype "passive"))
    )
    (net (code "43") (name "Net-(I5-Pad3)") (class "Default")
      (node (ref "I5") (pin "3") (pinfunction "3_3") (pintype "passive"))
      (node (ref "R23") (pin "2") (pinfunction "2_2") (pintype "passive"))
    )
    (net (code "44") (name "Net-(I6-Pad3)") (class "Default")
      (node (ref "I6") (pin "3") (pinfunction "3_3") (pintype "passive"))
      (node (ref "R20") (pin "2") (pinfunction "2_2") (pintype "passive"))
    )
    (net (code "45") (name "Net-(I7-Pad3)") (class "Default")
      (node (ref "I7") (pin "3") (pinfunction "3_3") (pintype "passive"))
      (node (ref "R19") (pin "2") (pinfunction "2_2") (pintype "passive"))
    )
    (net (code "46") (name "Net-(I8-Pad3)") (class "Default")
      (node (ref "I8") (pin "3") (pinfunction "3_3") (pintype "passive"))
      (node (ref "R16") (pin "2") (pinfunction "2_2") (pintype "passive"))
    )
    (net (code "47") (name "Net-(R1-Pad1)") (class "Default")
      (node (ref "R1") (pin "1") (pinfunction "1_1") (pintype "passive"))
      (node (ref "R8") (pin "2") (pinfunction "2_2") (pintype "passive"))
      (node (ref "U5") (pin "ADJ") (pinfunction "ADJ_ADJ") (pintype "input"))
    )
    (net (code "48") (name "Net-(R2-Pad1)") (class "Default")
      (node (ref "R2") (pin "1") (pinfunction "1_1") (pintype "passive"))
      (node (ref "STAT1") (pin "A") (pinfunction "A_A") (pintype "passive"))
    )
    (net (code "49") (name "Net-(R4-Pad1)") (class "Default")
      (node (ref "R4") (pin "1") (pinfunction "1_1") (pintype "passive"))
      (node (ref "STAT2") (pin "A") (pinfunction "A_A") (pintype "passive"))
    )
    (net (code "50") (name "Net-(R10-Pad1)") (class "Default")
      (node (ref "R10") (pin "1") (pinfunction "1_1") (pintype "passive"))
      (node (ref "STAT3") (pin "A") (pinfunction "A_A") (pintype "passive"))
    )
    (net (code "51") (name "Net-(R11-Pad1)") (class "Default")
      (node (ref "R11") (pin "1") (pinfunction "1_1") (pintype "passive"))
      (node (ref "STAT4") (pin "A") (pinfunction "A_A") (pintype "passive"))
    )
    (net (code "52") (name "Net-(U1C-MCLR)") (class "Default")
      (node (ref "R15") (pin "2") (pinfunction "2_2") (pintype "passive"))
      (node (ref "U1") (pin "13") (pinfunction "MCLR_13") (pintype "bidirectional"))
    )
    (net (code "53") (name "Net-(U1D-RC12{slash}OSC1)") (class "Default")
      (node (ref "U1") (pin "63") (pinfunction "RC12/OSC1_63") (pintype "bidirectional"))
      (node (ref "Y1") (pin "1") (pinfunction "1_1") (pintype "passive"))
    )
    (net (code "54") (name "Net-(U1D-RC15{slash}OSC2)") (class "Default")
      (node (ref "U1") (pin "64") (pinfunction "RC15/OSC2_64") (pintype "bidirectional"))
      (node (ref "Y1") (pin "3") (pinfunction "3_3") (pintype "passive"))
    )
    (net (code "55") (name "Net-(U6-VBAT)") (class "Default")
      (node (ref "C12") (pin "+") (pinfunction "+_+") (pintype "passive"))
      (node (ref "U6") (pin "2") (pinfunction "VBAT_2") (pintype "bidirectional"))
    )
    (net (code "56") (name "Net-(U10-CPOUT)") (class "Default")
      (node (ref "C2") (pin "1") (pinfunction "1_1") (pintype "passive"))
      (node (ref "U10") (pin "20") (pinfunction "CPOUT_20") (pintype "bidirectional"))
    )
    (net (code "57") (name "Net-(U10-CS)") (class "Default")
      (node (ref "R25") (pin "2") (pinfunction "2_2") (pintype "passive"))
      (node (ref "U10") (pin "8") (pinfunction "CS_8") (pintype "bidirectional"))
    )
    (net (code "58") (name "Net-(U10-REGOUT)") (class "Default")
      (node (ref "C9") (pin "1") (pinfunction "1_1") (pintype "passive"))
      (node (ref "U10") (pin "10") (pinfunction "REGOUT_10") (pintype "bidirectional"))
    )
    (net (code "59") (name "O1") (class "Default")
      (node (ref "O1") (pin "3") (pinfunction "3_3") (pintype "passive"))
      (node (ref "U1") (pin "72") (pinfunction "RD0/OC1_72") (pintype "bidirectional"))
    )
    (net (code "60") (name "O2") (class "Default")
      (node (ref "O2") (pin "3") (pinfunction "3_3") (pintype "passive"))
      (node (ref "U1") (pin "76") (pinfunction "RD1/OC2_76") (pintype "bidirectional"))
    )
    (net (code "61") (name "O3") (class "Default")
      (node (ref "O3") (pin "3") (pinfunction "3_3") (pintype "passive"))
      (node (ref "U1") (pin "77") (pinfunction "RD2/OC3_77") (pintype "bidirectional"))
    )
    (net (code "62") (name "O4") (class "Default")
      (node (ref "O4") (pin "3") (pinfunction "3_3") (pintype "passive"))
      (node (ref "U1") (pin "78") (pinfunction "RD3/OC4_78") (pintype "bidirectional"))
    )
    (net (code "63") (name "O5") (class "Default")
      (node (ref "O5") (pin "3") (pinfunction "3_3") (pintype "passive"))
      (node (ref "U1") (pin "81") (pinfunction "RD4/OC5_81") (pintype "bidirectional"))
    )
    (net (code "64") (name "O6") (class "Default")
      (node (ref "O6") (pin "3") (pinfunction "3_3") (pintype "passive"))
      (node (ref "U1") (pin "82") (pinfunction "RD5/OC6_82") (pintype "bidirectional"))
    )
    (net (code "65") (name "O7") (class "Default")
      (node (ref "O7") (pin "3") (pinfunction "3_3") (pintype "passive"))
      (node (ref "U1") (pin "83") (pinfunction "RD6/OC7_83") (pintype "bidirectional"))
    )
    (net (code "66") (name "O8") (class "Default")
      (node (ref "O8") (pin "3") (pinfunction "3_3") (pintype "passive"))
      (node (ref "U1") (pin "84") (pinfunction "RD7/OC8_84") (pintype "bidirectional"))
    )
    (net (code "67") (name "PGEC2") (class "Default")
      (node (ref "JP2") (pin "2") (pinfunction "2_2") (pintype "passive"))
      (node (ref "U1") (pin "74") (pinfunction "RC14/PGEC2_74") (pintype "bidirectional"))
    )
    (net (code "68") (name "PGED2") (class "Default")
      (node (ref "JP2") (pin "3") (pinfunction "3_3") (pintype "passive"))
      (node (ref "U1") (pin "73") (pinfunction "RC13/PGED2_73") (pintype "bidirectional"))
    )
    (net (code "69") (name "RA1") (class "Default")
      (node (ref "JP15") (pin "2") (pinfunction "2_2") (pintype "passive"))
      (node (ref "U1") (pin "38") (pinfunction "RA1_38") (pintype "bidirectional"))
    )
    (net (code "70") (name "RA4") (class "Default")
      (node (ref "JP15") (pin "3") (pinfunction "3_3") (pintype "passive"))
      (node (ref "U1") (pin "60") (pinfunction "RA4/TDI_60") (pintype "bidirectional"))
    )
    (net (code "71") (name "RA5") (class "Default")
      (node (ref "JP7") (pin "1") (pinfunction "1_1") (pintype "passive"))
      (node (ref "U1") (pin "61") (pinfunction "RA5/TDO_61") (pintype "bidirectional"))
    )
    (net (code "72") (name "RTS2") (class "Default")
      (node (ref "JP5") (pin "2") (pinfunction "2_2") (pintype "passive"))
      (node (ref "U1") (pin "39") (pinfunction "RF13/U2RTS_39") (pintype "bidirectional"))
    )
    (net (code "73") (name "RX2") (class "Default")
      (node (ref "JP5") (pin "4") (pinfunction "4_4") (pintype "passive"))
      (node (ref "U1") (pin "49") (pinfunction "RF4/U2RX_49") (pintype "bidirectional"))
    )
    (net (code "74") (name "SCK1") (class "Default")
      (node (ref "JP8") (pin "1") (pinfunction "1_1") (pintype "passive"))
      (node (ref "U1") (pin "55") (pinfunction "RF6/SCK1_55") (pintype "bidirectional"))
    )
    (net (code "75") (name "SCL1") (class "Default")
      (node (ref "R13") (pin "1") (pinfunction "1_1") (pintype "passive"))
      (node (ref "U1") (pin "57") (pinfunction "RG2/SCL1_57") (pintype "bidirectional"))
      (node (ref "U8") (pin "6") (pinfunction "SCL_6") (pintype "bidirectional"))
    )
    (net (code "76") (name "SCL2") (class "Default")
      (node (ref "JP11") (pin "1") (pinfunction "1_1") (pintype "passive"))
      (node (ref "R7") (pin "1") (pinfunction "1_1") (pintype "passive"))
      (node (ref "U1") (pin "58") (pinfunction "RA2/SCL2_58") (pintype "bidirectional"))
    )
    (net (code "77") (name "SDA1") (class "Default")
      (node (ref "R14") (pin "1") (pinfunction "1_1") (pintype "passive"))
      (node (ref "U1") (pin "56") (pinfunction "RG3/SDA1_56") (pintype "bidirectional"))
      (node (ref "U8") (pin "5") (pinfunction "SDA_5") (pintype "bidirectional"))
    )
    (net (code "78") (name "SDA2") (class "Default")
      (node (ref "JP11") (pin "2") (pinfunction "2_2") (pintype "passive"))
      (node (ref "R9") (pin "1") (pinfunction "1_1") (pintype "passive"))
      (node (ref "U1") (pin "59") (pinfunction "RA3/SDA2_59") (pintype "bidirectional"))
    )
    (net (code "79") (name "SDI1") (class "Default")
      (node (ref "JP8") (pin "3") (pinfunction "3_3") (pintype "passive"))
      (node (ref "U1") (pin "54") (pinfunction "RF7/SDI1_54") (pintype "bidirectional"))
    )
    (net (code "80") (name "SDO1") (class "Default")
      (node (ref "JP8") (pin "2") (pinfunction "2_2") (pintype "passive"))
      (node (ref "U1") (pin "53") (pinfunction "RF8/SDO1_53") (pintype "bidirectional"))
    )
    (net (code "81") (name "SS1") (class "Default")
      (node (ref "JP8") (pin "4") (pinfunction "4_4") (pintype "passive"))
      (node (ref "U1") (pin "23") (pinfunction "RB2/SS1_23") (pintype "bidirectional"))
    )
    (net (code "82") (name "SVCC") (class "Default")
      (node (ref "JP4") (pin "2") (pinfunction "2_2") (pintype "passive"))
      (node (ref "O1") (pin "2") (pinfunction "2_2") (pintype "passive"))
      (node (ref "O2") (pin "2") (pinfunction "2_2") (pintype "passive"))
      (node (ref "O3") (pin "2") (pinfunction "2_2") (pintype "passive"))
      (node (ref "O4") (pin "2") (pinfunction "2_2") (pintype "passive"))
      (node (ref "O5") (pin "2") (pinfunction "2_2") (pintype "passive"))
      (node (ref "O6") (pin "2") (pinfunction "2_2") (pintype "passive"))
      (node (ref "O7") (pin "2") (pinfunction "2_2") (pintype "passive"))
      (node (ref "O8") (pin "2") (pinfunction "2_2") (pintype "passive"))
      (node (ref "OUTPUT1") (pin "1") (pinfunction "1_1") (pintype "passive"))
      (node (ref "OUTPUT2") (pin "A") (pinfunction "+_A") (pintype "passive"))
      (node (ref "SJ1") (pin "2") (pinfunction "2_2") (pintype "passive"))
    )
    (net (code "83") (name "TX2") (class "Default")
      (node (ref "JP5") (pin "3") (pinfunction "3_3") (pintype "passive"))
      (node (ref "U1") (pin "50") (pinfunction "RF5/U2TX_50") (pintype "bidirectional"))
    )
    (net (code "84") (name "VCC") (class "Default")
      (node (ref "C3") (pin "1") (pinfunction "1_1") (pintype "passive"))
      (node (ref "C5") (pin "A") (pinfunction "+_A") (pintype "passive"))
      (node (ref "C7") (pin "1") (pinfunction "1_1") (pintype "passive"))
      (node (ref "I1") (pin "2") (pinfunction "2_2") (pintype "passive"))
      (node (ref "I2") (pin "2") (pinfunction "2_2") (pintype "passive"))
      (node (ref "I3") (pin "2") (pinfunction "2_2") (pintype "passive"))
      (node (ref "I4") (pin "2") (pinfunction "2_2") (pintype "passive"))
      (node (ref "I5") (pin "2") (pinfunction "2_2") (pintype "passive"))
      (node (ref "I6") (pin "2") (pinfunction "2_2") (pintype "passive"))
      (node (ref "I7") (pin "2") (pinfunction "2_2") (pintype "passive"))
      (node (ref "I8") (pin "2") (pinfunction "2_2") (pintype "passive"))
      (node (ref "INPUT1") (pin "1") (pinfunction "1_1") (pintype "passive"))
      (node (ref "INPUT2") (pin "1") (pinfunction "1_1") (pintype "passive"))
      (node (ref "R3") (pin "2") (pinfunction "2_2") (pintype "passive"))
      (node (ref "SJ1") (pin "1") (pinfunction "1_1") (pintype "passive"))
      (node (ref "U3") (pin "1") (pinfunction "IN_1") (pintype "input"))
      (node (ref "U3") (pin "3") (pinfunction "EN_3") (pintype "input"))
      (node (ref "U5") (pin "EN") (pinfunction "EN_EN") (pintype "bidirectional"))
      (node (ref "U5") (pin "VIN") (pinfunction "IN_VIN") (pintype "input"))
    )
    (net (code "85") (name "unconnected-(JP2-Pad1)") (class "Default")
      (node (ref "JP2") (pin "1") (pinfunction "1_1") (pintype "passive"))
    )
    (net (code "86") (name "unconnected-(JP15-Pad1)") (class "Default")
      (node (ref "JP15") (pin "1") (pinfunction "1_1") (pintype "passive"))
    )
    (net (code "87") (name "unconnected-(U1A-RA9{slash}VREF--Pad28)") (class "Default")
      (node (ref "U1") (pin "28") (pinfunction "RA9/VREF-_28") (pintype "bidirectional"))
    )
    (net (code "88") (name "unconnected-(U1A-RA10{slash}VREF+-Pad29)") (class "Default")
      (node (ref "U1") (pin "29") (pinfunction "RA10/VREF+_29") (pintype "bidirectional"))
    )
    (net (code "89") (name "unconnected-(U1B-RA6{slash}AN22-Pad91)") (class "Default")
      (node (ref "U1") (pin "91") (pinfunction "RA6/AN22_91") (pintype "bidirectional"))
    )
    (net (code "90") (name "unconnected-(U1B-RB3{slash}AN3-Pad22)") (class "Default")
      (node (ref "U1") (pin "22") (pinfunction "RB3/AN3_22") (pintype "bidirectional"))
    )
    (net (code "91") (name "unconnected-(U1B-RB4{slash}AN4-Pad21)") (class "Default")
      (node (ref "U1") (pin "21") (pinfunction "RB4/AN4_21") (pintype "bidirectional"))
    )
    (net (code "92") (name "unconnected-(U1B-RB5{slash}AN5-Pad20)") (class "Default")
      (node (ref "U1") (pin "20") (pinfunction "RB5/AN5_20") (pintype "bidirectional"))
    )
    (net (code "93") (name "unconnected-(U1B-RB6{slash}AN6-Pad26)") (class "Default")
      (node (ref "U1") (pin "26") (pinfunction "RB6/AN6_26") (pintype "bidirectional"))
    )
    (net (code "94") (name "unconnected-(U1B-RB7{slash}AN7-Pad27)") (class "Default")
      (node (ref "U1") (pin "27") (pinfunction "RB7/AN7_27") (pintype "bidirectional"))
    )
    (net (code "95") (name "unconnected-(U1B-RB8{slash}AN8-Pad32)") (class "Default")
      (node (ref "U1") (pin "32") (pinfunction "RB8/AN8_32") (pintype "bidirectional"))
    )
    (net (code "96") (name "unconnected-(U1B-RB9{slash}AN9-Pad33)") (class "Default")
      (node (ref "U1") (pin "33") (pinfunction "RB9/AN9_33") (pintype "bidirectional"))
    )
    (net (code "97") (name "unconnected-(U1B-RB10{slash}AN10-Pad34)") (class "Default")
      (node (ref "U1") (pin "34") (pinfunction "RB10/AN10_34") (pintype "bidirectional"))
    )
    (net (code "98") (name "unconnected-(U1B-RB11{slash}AN11-Pad35)") (class "Default")
      (node (ref "U1") (pin "35") (pinfunction "RB11/AN11_35") (pintype "bidirectional"))
    )
    (net (code "99") (name "unconnected-(U1B-RB12{slash}AN12-Pad41)") (class "Default")
      (node (ref "U1") (pin "41") (pinfunction "RB12/AN12_41") (pintype "bidirectional"))
    )
    (net (code "100") (name "unconnected-(U1B-RB13{slash}AN13-Pad42)") (class "Default")
      (node (ref "U1") (pin "42") (pinfunction "RB13/AN13_42") (pintype "bidirectional"))
    )
    (net (code "101") (name "unconnected-(U1B-RB14{slash}AN14-Pad43)") (class "Default")
      (node (ref "U1") (pin "43") (pinfunction "RB14/AN14_43") (pintype "bidirectional"))
    )
    (net (code "102") (name "unconnected-(U1B-RC4{slash}AN19-Pad9)") (class "Default")
      (node (ref "U1") (pin "9") (pinfunction "RC4/AN19_9") (pintype "bidirectional"))
    )
    (net (code "103") (name "unconnected-(U1D-RA0{slash}TMS-Pad17)") (class "Default")
      (node (ref "U1") (pin "17") (pinfunction "RA0/TMS_17") (pintype "bidirectional"))
    )
    (net (code "104") (name "unconnected-(U1D-RE5{slash}AN29-Pad3)") (class "Default")
      (node (ref "U1") (pin "3") (pinfunction "RE5/AN29_3") (pintype "bidirectional"))
    )
    (net (code "105") (name "unconnected-(U1D-RE6{slash}AN30-Pad4)") (class "Default")
      (node (ref "U1") (pin "4") (pinfunction "RE6/AN30_4") (pintype "bidirectional"))
    )
    (net (code "106") (name "unconnected-(U1D-RE7{slash}AN31-Pad5)") (class "Default")
      (node (ref "U1") (pin "5") (pinfunction "RE7/AN31_5") (pintype "bidirectional"))
    )
    (net (code "107") (name "unconnected-(U1D-RG0{slash}C2RX-Pad90)") (class "Default")
      (node (ref "U1") (pin "90") (pinfunction "RG0/C2RX_90") (pintype "bidirectional"))
    )
    (net (code "108") (name "unconnected-(U1D-RG1{slash}C2TX-Pad89)") (class "Default")
      (node (ref "U1") (pin "89") (pinfunction "RG1/C2TX_89") (pintype "bidirectional"))
    )
    (net (code "109") (name "unconnected-(U1D-RG12{slash}CSDI-Pad96)") (class "Default")
      (node (ref "U1") (pin "96") (pinfunction "RG12/CSDI_96") (pintype "bidirectional"))
    )
    (net (code "110") (name "unconnected-(U1D-RG13{slash}CSDO-Pad97)") (class "Default")
      (node (ref "U1") (pin "97") (pinfunction "RG13/CSDO_97") (pintype "bidirectional"))
    )
    (net (code "111") (name "unconnected-(U1D-RG14{slash}CSCK-Pad95)") (class "Default")
      (node (ref "U1") (pin "95") (pinfunction "RG14/CSCK_95") (pintype "bidirectional"))
    )
    (net (code "112") (name "unconnected-(U1D-RG15{slash}COFS-Pad1)") (class "Default")
      (node (ref "U1") (pin "1") (pinfunction "RG15/COFS_1") (pintype "bidirectional"))
    )
    (net (code "113") (name "unconnected-(U3-BP-Pad4)") (class "Default")
      (node (ref "U3") (pin "4") (pinfunction "BP_4") (pintype "input"))
    )
    (net (code "114") (name "unconnected-(U6-LED-Pad1)") (class "Default")
      (node (ref "U6") (pin "1") (pinfunction "LED_1") (pintype "bidirectional"))
    )
    (net (code "115") (name "unconnected-(U10-AUXCL-Pad7)") (class "Default")
      (node (ref "U10") (pin "7") (pinfunction "AUXCL_7") (pintype "bidirectional"))
    )
    (net (code "116") (name "unconnected-(U10-AUXDA-Pad6)") (class "Default")
      (node (ref "U10") (pin "6") (pinfunction "AUXDA_6") (pintype "bidirectional"))
    )
    (net (code "117") (name "unconnected-(U10-CLKOUT-Pad22)") (class "Default")
      (node (ref "U10") (pin "22") (pinfunction "CLKOUT_22") (pintype "bidirectional"))
    )
  )
)
